# FreedomPort.net
KiCad netlist of a schematic drawn in EAGLE
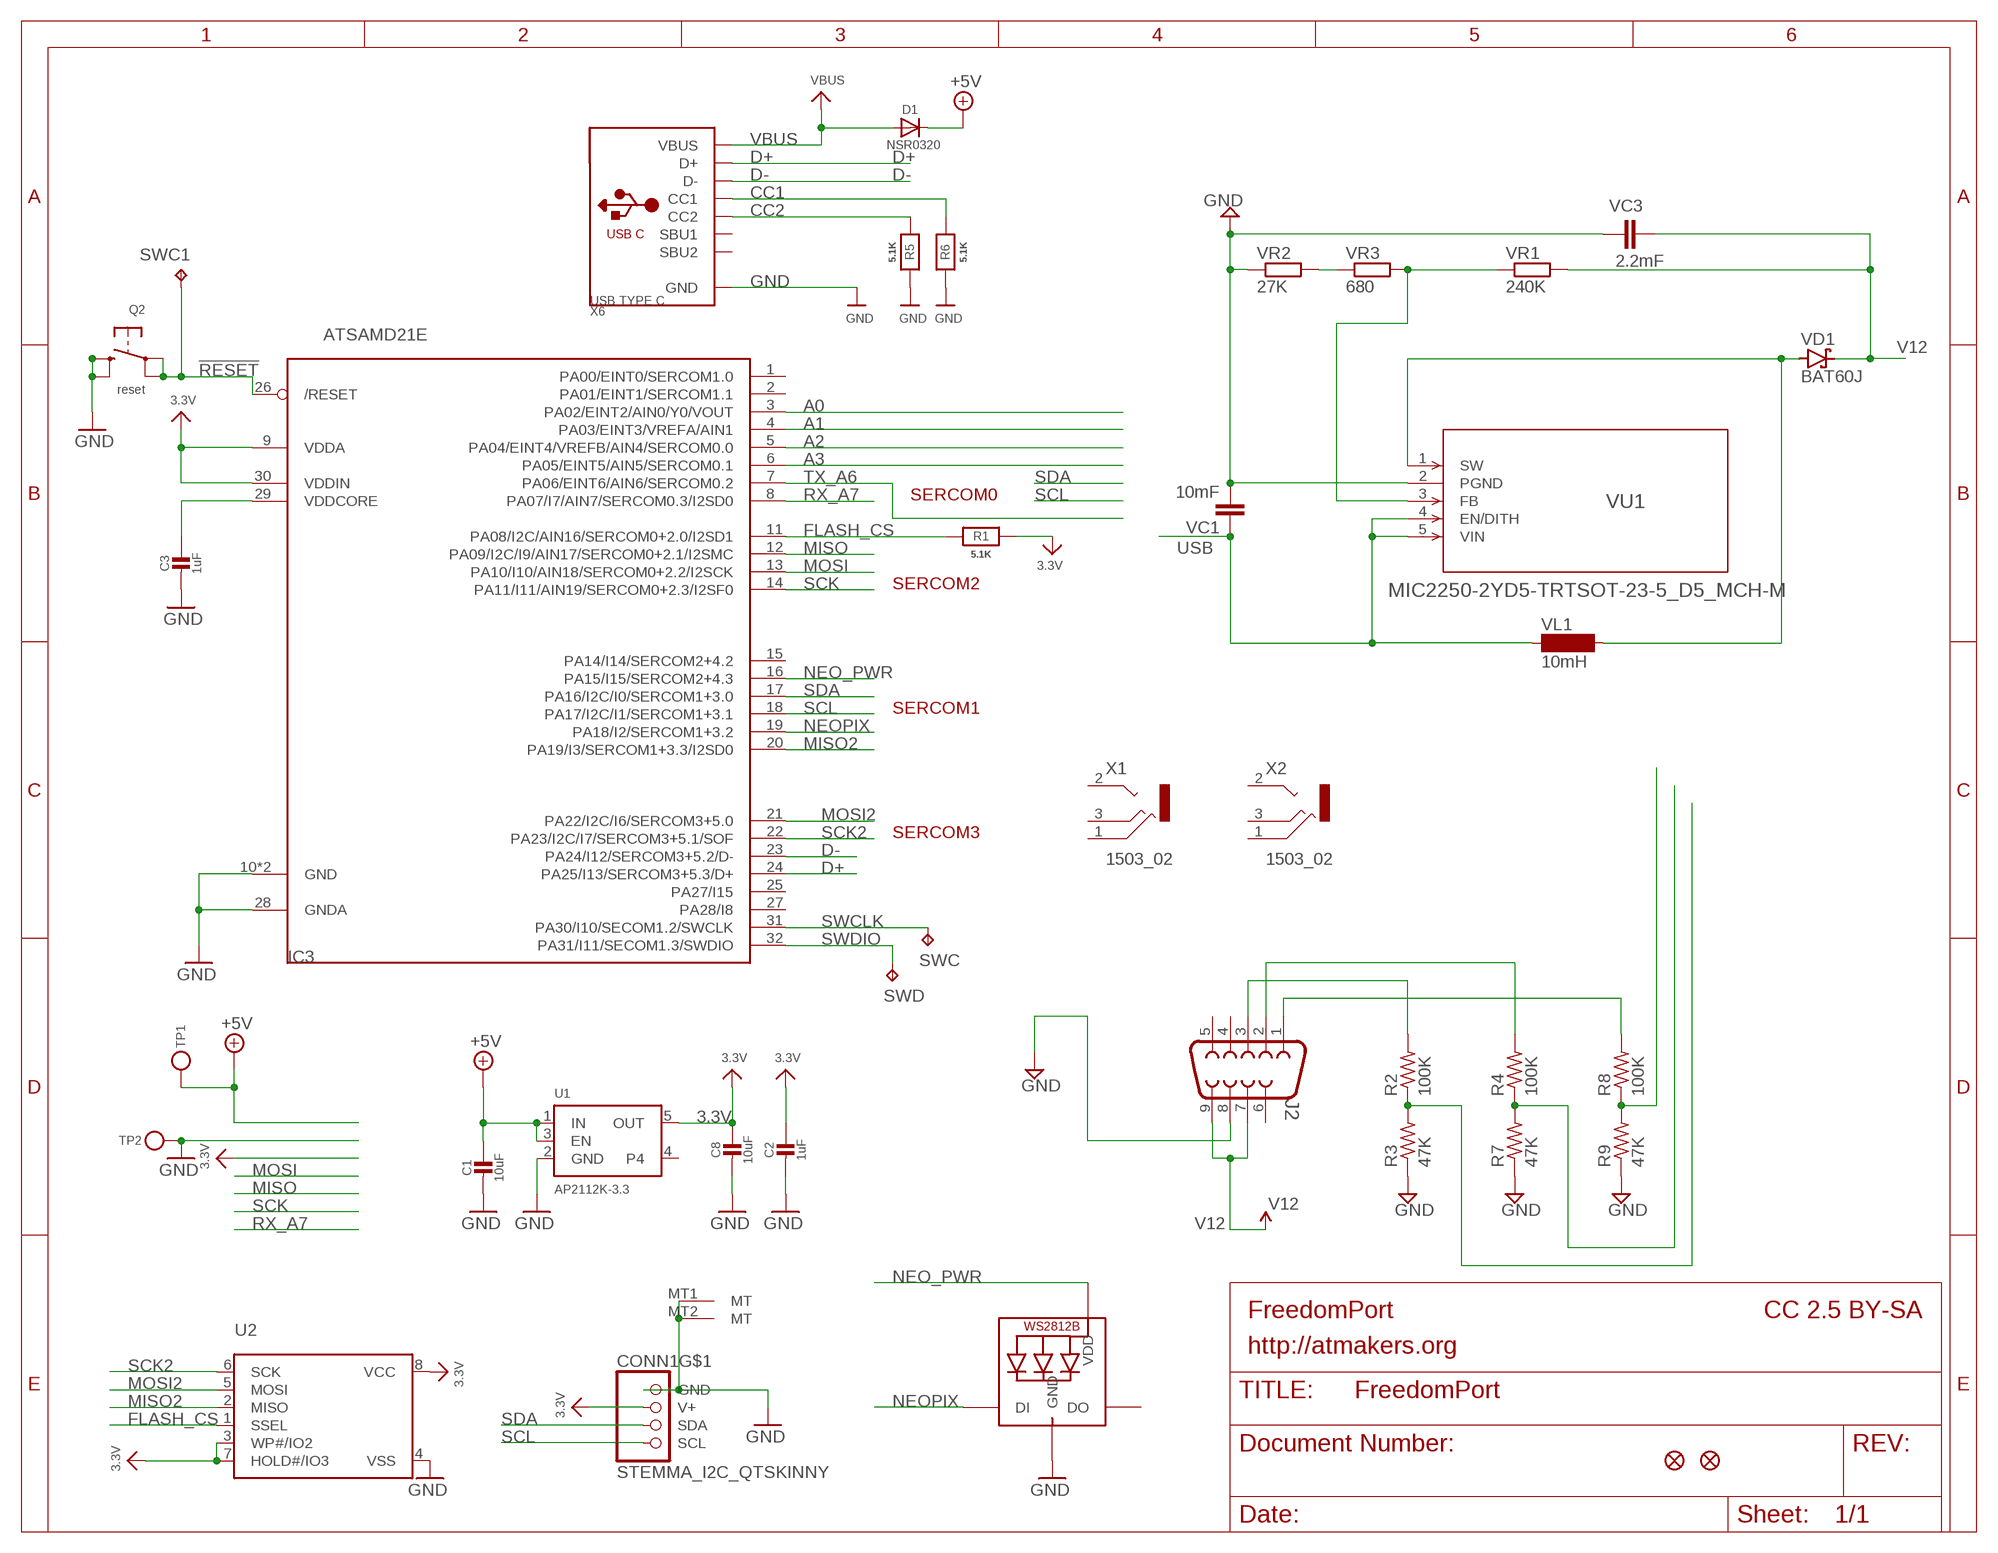
[diagram p0: schematic, sheet 1]

(export (version "E")
  (design (tool "Eeschema 10.0.6"))
  (components
    (comp (ref "C1")
      (value "10uF")
      (footprint "eagle-import:_0805MP")
      (libsource (lib "eagle-import") (part "CAP_CERAMIC_0805MP"))
    )
    (comp (ref "C2")
      (value "1uF")
      (footprint "eagle-import:_0402NO")
      (libsource (lib "eagle-import") (part "CAP_CERAMIC_0402NO"))
    )
    (comp (ref "C3")
      (value "1uF")
      (footprint "eagle-import:_0402NO")
      (libsource (lib "eagle-import") (part "CAP_CERAMIC_0402NO"))
    )
    (comp (ref "C8")
      (value "10uF")
      (footprint "eagle-import:_0805MP")
      (libsource (lib "eagle-import") (part "CAP_CERAMIC_0805MP"))
    )
    (comp (ref "CONN1")
      (value "STEMMA_I2C_QTSKINNY")
      (footprint "eagle-import:JST_SH4_SKINNY")
      (libsource (lib "eagle-import") (part "STEMMA_I2C_QTSKINNY"))
    )
    (comp (ref "D1")
      (value "NSR0320")
      (footprint "eagle-import:SOD-323_MINI")
      (libsource (lib "eagle-import") (part "DIODE_SOD323MINI"))
    )
    (comp (ref "IC3")
      (value "ATSAMD21E")
      (footprint "eagle-import:QFN32_5MM")
      (libsource (lib "eagle-import") (part "ATSAMD21E"))
    )
    (comp (ref "J2")
      (value "DB9MALE")
      (footprint "eagle-import:DB9_MALE")
      (libsource (lib "eagle-import") (part "DB9MALE"))
    )
    (comp (ref "LED1")
      (value "WS2812B_SK6805_1515")
      (footprint "eagle-import:SK6805_1515")
      (libsource (lib "eagle-import") (part "WS2812B_SK6805_1515"))
    )
    (comp (ref "Q2")
      (value "reset")
      (footprint "eagle-import:BTN_KMR2_4.6X2.8")
      (libsource (lib "eagle-import") (part "SWITCH_TACT_SMT4.6X2.8"))
    )
    (comp (ref "R1")
      (value "5.1K")
      (footprint "eagle-import:_0402NO")
      (libsource (lib "eagle-import") (part "RESISTOR_0402NO"))
    )
    (comp (ref "R2")
      (value "100K")
      (footprint "eagle-import:R0805")
      (libsource (lib "eagle-import") (part "R-US_R0805"))
    )
    (comp (ref "R3")
      (value "47K")
      (footprint "eagle-import:R0805")
      (libsource (lib "eagle-import") (part "R-US_R0805"))
    )
    (comp (ref "R4")
      (value "100K")
      (footprint "eagle-import:R0805")
      (libsource (lib "eagle-import") (part "R-US_R0805"))
    )
    (comp (ref "R5")
      (value "5.1K")
      (footprint "eagle-import:_0402NO")
      (libsource (lib "eagle-import") (part "RESISTOR_0402NO"))
    )
    (comp (ref "R6")
      (value "5.1K")
      (footprint "eagle-import:_0402NO")
      (libsource (lib "eagle-import") (part "RESISTOR_0402NO"))
    )
    (comp (ref "R7")
      (value "47K")
      (footprint "eagle-import:R0805")
      (libsource (lib "eagle-import") (part "R-US_R0805"))
    )
    (comp (ref "R8")
      (value "100K")
      (footprint "eagle-import:R0805")
      (libsource (lib "eagle-import") (part "R-US_R0805"))
    )
    (comp (ref "R9")
      (value "47K")
      (footprint "eagle-import:R0805")
      (libsource (lib "eagle-import") (part "R-US_R0805"))
    )
    (comp (ref "SWC")
      (value "TPB1,27")
      (footprint "eagle-import:B1,27")
      (libsource (lib "eagle-import") (part "TPB1,27"))
    )
    (comp (ref "SWC1")
      (value "TPB1,27")
      (footprint "eagle-import:B1,27")
      (libsource (lib "eagle-import") (part "TPB1,27"))
    )
    (comp (ref "SWD")
      (value "TPB1,27")
      (footprint "eagle-import:B1,27")
      (libsource (lib "eagle-import") (part "TPB1,27"))
    )
    (comp (ref "TP1")
      (value "TESTPOINT_1X3")
      (footprint "eagle-import:TESTPOINT_RECT_1X3MM")
      (libsource (lib "eagle-import") (part "TESTPOINT_1X3"))
    )
    (comp (ref "TP2")
      (value "TESTPOINT_1X3")
      (footprint "eagle-import:TESTPOINT_RECT_1X3MM")
      (libsource (lib "eagle-import") (part "TESTPOINT_1X3"))
    )
    (comp (ref "U$6")
      (value "FIDUCIAL_1MM")
      (footprint "eagle-import:FIDUCIAL_1MM")
      (libsource (lib "eagle-import") (part "FIDUCIAL_1MM"))
    )
    (comp (ref "U$8")
      (value "FIDUCIAL_1MM")
      (footprint "eagle-import:FIDUCIAL_1MM")
      (libsource (lib "eagle-import") (part "FIDUCIAL_1MM"))
    )
    (comp (ref "U1")
      (value "AP2112K-3.3")
      (footprint "eagle-import:SOT23-5")
      (libsource (lib "eagle-import") (part "VREG_SOT23-5"))
    )
    (comp (ref "U2")
      (value "SPIFLASH_8PIN")
      (footprint "eagle-import:SOIC8_150MIL")
      (libsource (lib "eagle-import") (part "SPIFLASH_8PIN"))
    )
    (comp (ref "VC1")
      (value "10mF")
      (footprint "eagle-import:C0805")
      (libsource (lib "eagle-import") (part "C-EUC0805"))
    )
    (comp (ref "VC3")
      (value "2.2mF")
      (footprint "eagle-import:C0805")
      (libsource (lib "eagle-import") (part "C-EUC0805"))
    )
    (comp (ref "VD1")
      (value "BAT60J")
      (footprint "eagle-import:SOD323_ST")
      (libsource (lib "eagle-import") (part "BAT60J"))
    )
    (comp (ref "VL1")
      (value "10mH")
      (footprint "eagle-import:MS50")
      (libsource (lib "eagle-import") (part "MS50"))
    )
    (comp (ref "VR1")
      (value "240K")
      (footprint "eagle-import:R0805W")
      (libsource (lib "eagle-import") (part "R-EU_R0805W"))
    )
    (comp (ref "VR2")
      (value "27K")
      (footprint "eagle-import:R0805W")
      (libsource (lib "eagle-import") (part "R-EU_R0805W"))
    )
    (comp (ref "VR3")
      (value "680")
      (footprint "eagle-import:R0805W")
      (libsource (lib "eagle-import") (part "R-EU_R0805W"))
    )
    (comp (ref "VU1")
      (value "MIC2250-2YD5-TRTSOT-23-5_D5_MCH-M")
      (footprint "eagle-import:TSOT-23-5_D5_MCH-M")
      (fields
        (field (name "MANUFACTURER_PART_NUMBER") "MIC2250-2YD5-TR")
        (field (name "COPYRIGHT") "Copyright (C) 2018 Accelerated Designs. All rights reserved")
      )
      (libsource (lib "eagle-import") (part "MIC2250-2YD5-TRTSOT-23-5_D5_MCH-M"))
    )
    (comp (ref "X1")
      (value "1503_02")
      (footprint "eagle-import:1503_02")
      (libsource (lib "eagle-import") (part "1503_02"))
    )
    (comp (ref "X2")
      (value "1503_02")
      (footprint "eagle-import:1503_02")
      (libsource (lib "eagle-import") (part "1503_02"))
    )
    (comp (ref "X6")
      (value "USB TYPE C")
      (footprint "eagle-import:USB_C_CUSB31-CFM2AX-01-X")
      (libsource (lib "eagle-import") (part "USB_C"))
    )
  )
  (nets
    (net (code "1") (name "+5V") (class "Default")
      (node (ref "C1") (pin "1") (pinfunction "1_1") (pintype "passive"))
      (node (ref "D1") (pin "C") (pinfunction "C_C") (pintype "passive"))
      (node (ref "TP1") (pin "P$1") (pinfunction "P$1_P$1") (pintype "bidirectional"))
      (node (ref "U1") (pin "1") (pinfunction "IN_1") (pintype "power_in"))
      (node (ref "U1") (pin "3") (pinfunction "EN_3") (pintype "input"))
    )
    (net (code "2") (name "/A0") (class "Default")
      (node (ref "IC3") (pin "3") (pinfunction "PA02/EINT2/AIN0/Y0/VOUT_3") (pintype "bidirectional"))
    )
    (net (code "3") (name "/A1") (class "Default")
      (node (ref "IC3") (pin "4") (pinfunction "PA03/EINT3/VREFA/AIN1_4") (pintype "bidirectional"))
    )
    (net (code "4") (name "/A2") (class "Default")
      (node (ref "IC3") (pin "5") (pinfunction "PA04/EINT4/VREFB/AIN4/SERCOM0.0_5") (pintype "bidirectional"))
    )
    (net (code "5") (name "/A3") (class "Default")
      (node (ref "IC3") (pin "6") (pinfunction "PA05/EINT5/AIN5/SERCOM0.1_6") (pintype "bidirectional"))
    )
    (net (code "6") (name "/CC1") (class "Default")
      (node (ref "R6") (pin "2") (pinfunction "2_2") (pintype "passive"))
      (node (ref "X6") (pin "A5") (pinfunction "CC1_A5") (pintype "bidirectional"))
    )
    (net (code "7") (name "/CC2") (class "Default")
      (node (ref "R5") (pin "2") (pinfunction "2_2") (pintype "passive"))
      (node (ref "X6") (pin "B5") (pinfunction "CC2_B5") (pintype "bidirectional"))
    )
    (net (code "8") (name "/D+") (class "Default")
      (node (ref "IC3") (pin "24") (pinfunction "PA25/I13/SERCOM3+5.3/D+_24") (pintype "bidirectional"))
      (node (ref "X6") (pin "A6") (pinfunction "D+_A6") (pintype "bidirectional"))
      (node (ref "X6") (pin "B6") (pinfunction "D+_B6") (pintype "bidirectional"))
    )
    (net (code "9") (name "/D-") (class "Default")
      (node (ref "IC3") (pin "23") (pinfunction "PA24/I12/SERCOM3+5.2/D-_23") (pintype "bidirectional"))
      (node (ref "X6") (pin "A7") (pinfunction "D-_A7") (pintype "bidirectional"))
      (node (ref "X6") (pin "B7") (pinfunction "D-_B7") (pintype "bidirectional"))
    )
    (net (code "10") (name "/FLASH_CS") (class "Default")
      (node (ref "IC3") (pin "11") (pinfunction "PA08/I2C/AIN16/SERCOM0+2.0/I2SD1_11") (pintype "bidirectional"))
      (node (ref "R1") (pin "2") (pinfunction "2_2") (pintype "passive"))
      (node (ref "U2") (pin "1") (pinfunction "SSEL_1") (pintype "bidirectional"))
    )
    (net (code "11") (name "/MISO") (class "Default")
      (node (ref "IC3") (pin "12") (pinfunction "PA09/I2C/I9/AIN17/SERCOM0+2.1/I2SMC_12") (pintype "bidirectional"))
    )
    (net (code "12") (name "/MISO2") (class "Default")
      (node (ref "IC3") (pin "20") (pinfunction "PA19/I3/SERCOM1+3.3/I2SD0_20") (pintype "bidirectional"))
      (node (ref "U2") (pin "2") (pinfunction "MISO_2") (pintype "bidirectional"))
    )
    (net (code "13") (name "/MOSI") (class "Default")
      (node (ref "IC3") (pin "13") (pinfunction "PA10/I10/AIN18/SERCOM0+2.2/I2SCK_13") (pintype "bidirectional"))
    )
    (net (code "14") (name "/MOSI2") (class "Default")
      (node (ref "IC3") (pin "21") (pinfunction "PA22/I2C/I6/SERCOM3+5.0_21") (pintype "bidirectional"))
      (node (ref "U2") (pin "5") (pinfunction "MOSI_5") (pintype "bidirectional"))
    )
    (net (code "15") (name "/NEOPIX") (class "Default")
      (node (ref "IC3") (pin "19") (pinfunction "PA18/I2/SERCOM1+3.2_19") (pintype "bidirectional"))
      (node (ref "LED1") (pin "1") (pinfunction "DI_1") (pintype "input"))
    )
    (net (code "16") (name "/NEO_PWR") (class "Default")
      (node (ref "IC3") (pin "16") (pinfunction "PA15/I15/SERCOM2+4.3_16") (pintype "bidirectional"))
      (node (ref "LED1") (pin "2") (pinfunction "VDD_2") (pintype "power_in"))
    )
    (net (code "17") (name "/RX_A7") (class "Default")
      (node (ref "IC3") (pin "8") (pinfunction "PA07/I7/AIN7/SERCOM0.3/I2SD0_8") (pintype "bidirectional"))
    )
    (net (code "18") (name "/SCK") (class "Default")
      (node (ref "IC3") (pin "14") (pinfunction "PA11/I11/AIN19/SERCOM0+2.3/I2SF0_14") (pintype "bidirectional"))
    )
    (net (code "19") (name "/SCK2") (class "Default")
      (node (ref "IC3") (pin "22") (pinfunction "PA23/I2C/I7/SERCOM3+5.1/SOF_22") (pintype "bidirectional"))
      (node (ref "U2") (pin "6") (pinfunction "SCK_6") (pintype "bidirectional"))
    )
    (net (code "20") (name "/SCL") (class "Default")
      (node (ref "CONN1") (pin "4") (pinfunction "SCL_4") (pintype "passive"))
      (node (ref "IC3") (pin "18") (pinfunction "PA17/I2C/I1/SERCOM1+3.1_18") (pintype "bidirectional"))
    )
    (net (code "21") (name "/SDA") (class "Default")
      (node (ref "CONN1") (pin "3") (pinfunction "SDA_3") (pintype "passive"))
      (node (ref "IC3") (pin "17") (pinfunction "PA16/I2C/I0/SERCOM1+3.0_17") (pintype "bidirectional"))
    )
    (net (code "22") (name "/SWCLK") (class "Default")
      (node (ref "IC3") (pin "31") (pinfunction "PA30/I10/SECOM1.2/SWCLK_31") (pintype "bidirectional"))
      (node (ref "SWC") (pin "TP") (pinfunction "TP_TP") (pintype "input"))
    )
    (net (code "23") (name "/SWDIO") (class "Default")
      (node (ref "IC3") (pin "32") (pinfunction "PA31/I11/SECOM1.3/SWDIO_32") (pintype "bidirectional"))
      (node (ref "SWD") (pin "TP") (pinfunction "TP_TP") (pintype "input"))
    )
    (net (code "24") (name "/TX_A6") (class "Default")
      (node (ref "IC3") (pin "7") (pinfunction "PA06/EINT6/AIN6/SERCOM0.2_7") (pintype "bidirectional"))
    )
    (net (code "25") (name "/USB") (class "Default")
      (node (ref "VC1") (pin "1") (pinfunction "1_1") (pintype "passive"))
      (node (ref "VL1") (pin "1") (pinfunction "1_1") (pintype "passive"))
      (node (ref "VU1") (pin "4") (pinfunction "EN/DITH_4") (pintype "input"))
      (node (ref "VU1") (pin "5") (pinfunction "VIN_5") (pintype "input"))
    )
    (net (code "26") (name "/~{RESET}") (class "Default")
      (node (ref "IC3") (pin "26") (pinfunction "/RESET_26") (pintype "bidirectional"))
      (node (ref "Q2") (pin "A") (pinfunction "P_A") (pintype "passive"))
      (node (ref "Q2") (pin "A'") (pinfunction "P1_A'") (pintype "passive"))
      (node (ref "SWC1") (pin "TP") (pinfunction "TP_TP") (pintype "input"))
    )
    (net (code "27") (name "3.3V") (class "Default")
      (node (ref "C2") (pin "1") (pinfunction "1_1") (pintype "passive"))
      (node (ref "C8") (pin "1") (pinfunction "1_1") (pintype "passive"))
      (node (ref "CONN1") (pin "2") (pinfunction "V+_2") (pintype "passive"))
      (node (ref "IC3") (pin "30") (pinfunction "VDDIN_30") (pintype "power_in"))
      (node (ref "IC3") (pin "9") (pinfunction "VDDA_9") (pintype "power_in"))
      (node (ref "R1") (pin "1") (pinfunction "1_1") (pintype "passive"))
      (node (ref "U1") (pin "5") (pinfunction "OUT_5") (pintype "power_in"))
      (node (ref "U2") (pin "3") (pinfunction "WP#/IO2_3") (pintype "bidirectional"))
      (node (ref "U2") (pin "7") (pinfunction "HOLD#/IO3_7") (pintype "bidirectional"))
      (node (ref "U2") (pin "8") (pinfunction "VCC_8") (pintype "bidirectional"))
    )
    (net (code "28") (name "GND") (class "Default")
      (node (ref "C1") (pin "2") (pinfunction "2_2") (pintype "passive"))
      (node (ref "C2") (pin "2") (pinfunction "2_2") (pintype "passive"))
      (node (ref "C3") (pin "2") (pinfunction "2_2") (pintype "passive"))
      (node (ref "C8") (pin "2") (pinfunction "2_2") (pintype "passive"))
      (node (ref "CONN1") (pin "1") (pinfunction "GND_1") (pintype "passive"))
      (node (ref "CONN1") (pin "MT1") (pinfunction "MT_MT1") (pintype "bidirectional"))
      (node (ref "CONN1") (pin "MT2") (pinfunction "MT_MT2") (pintype "bidirectional"))
      (node (ref "IC3") (pin "10") (pinfunction "GND_10") (pintype "power_in"))
      (node (ref "IC3") (pin "28") (pinfunction "GNDA_28") (pintype "power_in"))
      (node (ref "IC3") (pin "33") (pinfunction "GND_33") (pintype "power_in"))
      (node (ref "J2") (pin "8") (pinfunction "8_8") (pintype "passive"))
      (node (ref "LED1") (pin "4") (pinfunction "GND_4") (pintype "power_in"))
      (node (ref "Q2") (pin "B") (pinfunction "S_B") (pintype "passive"))
      (node (ref "Q2") (pin "B'") (pinfunction "S1_B'") (pintype "passive"))
      (node (ref "R3") (pin "1") (pinfunction "1_1") (pintype "passive"))
      (node (ref "R5") (pin "1") (pinfunction "1_1") (pintype "passive"))
      (node (ref "R6") (pin "1") (pinfunction "1_1") (pintype "passive"))
      (node (ref "R7") (pin "1") (pinfunction "1_1") (pintype "passive"))
      (node (ref "R9") (pin "1") (pinfunction "1_1") (pintype "passive"))
      (node (ref "TP2") (pin "P$1") (pinfunction "P$1_P$1") (pintype "bidirectional"))
      (node (ref "U1") (pin "2") (pinfunction "GND_2") (pintype "power_in"))
      (node (ref "U2") (pin "4") (pinfunction "VSS_4") (pintype "bidirectional"))
      (node (ref "VC1") (pin "2") (pinfunction "2_2") (pintype "passive"))
      (node (ref "VC3") (pin "1") (pinfunction "1_1") (pintype "passive"))
      (node (ref "VR2") (pin "1") (pinfunction "1_1") (pintype "passive"))
      (node (ref "VU1") (pin "2") (pinfunction "PGND_2") (pintype "power_in"))
      (node (ref "X6") (pin "A1B12") (pinfunction "GND_A1B12") (pintype "power_in"))
      (node (ref "X6") (pin "B1A12") (pinfunction "GND_B1A12") (pintype "power_in"))
    )
    (net (code "29") (name "Net-(IC3-VDDCORE)") (class "Default")
      (node (ref "C3") (pin "1") (pinfunction "1_1") (pintype "passive"))
      (node (ref "IC3") (pin "29") (pinfunction "VDDCORE_29") (pintype "power_in"))
    )
    (net (code "30") (name "Net-(J2-Pad1)") (class "Default")
      (node (ref "J2") (pin "1") (pinfunction "1_1") (pintype "passive"))
      (node (ref "R8") (pin "2") (pinfunction "2_2") (pintype "passive"))
    )
    (net (code "31") (name "Net-(J2-Pad2)") (class "Default")
      (node (ref "J2") (pin "2") (pinfunction "2_2") (pintype "passive"))
      (node (ref "R4") (pin "2") (pinfunction "2_2") (pintype "passive"))
    )
    (net (code "32") (name "Net-(J2-Pad3)") (class "Default")
      (node (ref "J2") (pin "3") (pinfunction "3_3") (pintype "passive"))
      (node (ref "R2") (pin "2") (pinfunction "2_2") (pintype "passive"))
    )
    (net (code "33") (name "Net-(R2-Pad1)") (class "Default")
      (node (ref "R2") (pin "1") (pinfunction "1_1") (pintype "passive"))
      (node (ref "R3") (pin "2") (pinfunction "2_2") (pintype "passive"))
    )
    (net (code "34") (name "Net-(R4-Pad1)") (class "Default")
      (node (ref "R4") (pin "1") (pinfunction "1_1") (pintype "passive"))
      (node (ref "R7") (pin "2") (pinfunction "2_2") (pintype "passive"))
    )
    (net (code "35") (name "Net-(R8-Pad1)") (class "Default")
      (node (ref "R8") (pin "1") (pinfunction "1_1") (pintype "passive"))
      (node (ref "R9") (pin "2") (pinfunction "2_2") (pintype "passive"))
    )
    (net (code "36") (name "Net-(VR2-Pad2)") (class "Default")
      (node (ref "VR2") (pin "2") (pinfunction "2_2") (pintype "passive"))
      (node (ref "VR3") (pin "1") (pinfunction "1_1") (pintype "passive"))
    )
    (net (code "37") (name "Net-(VU1-FB)") (class "Default")
      (node (ref "VR1") (pin "1") (pinfunction "1_1") (pintype "passive"))
      (node (ref "VR3") (pin "2") (pinfunction "2_2") (pintype "passive"))
      (node (ref "VU1") (pin "3") (pinfunction "FB_3") (pintype "input"))
    )
    (net (code "38") (name "Net-(VU1-SW)") (class "Default")
      (node (ref "VD1") (pin "A") (pinfunction "A_A") (pintype "passive"))
      (node (ref "VL1") (pin "2") (pinfunction "2_2") (pintype "passive"))
      (node (ref "VU1") (pin "1") (pinfunction "SW_1") (pintype "input"))
    )
    (net (code "39") (name "V12") (class "Default")
      (node (ref "J2") (pin "7") (pinfunction "7_7") (pintype "passive"))
      (node (ref "J2") (pin "9") (pinfunction "9_9") (pintype "passive"))
      (node (ref "VC3") (pin "2") (pinfunction "2_2") (pintype "passive"))
      (node (ref "VD1") (pin "C") (pinfunction "C_C") (pintype "passive"))
      (node (ref "VR1") (pin "2") (pinfunction "2_2") (pintype "passive"))
    )
    (net (code "40") (name "VBUS") (class "Default")
      (node (ref "D1") (pin "A") (pinfunction "A_A") (pintype "passive"))
      (node (ref "X6") (pin "A4B9") (pinfunction "VBUS_A4B9") (pintype "power_in"))
      (node (ref "X6") (pin "B4A9") (pinfunction "VBUS_B4A9") (pintype "power_in"))
    )
    (net (code "41") (name "unconnected-(IC3-PA00{slash}EINT0{slash}SERCOM1.0-Pad1)") (class "Default")
      (node (ref "IC3") (pin "1") (pinfunction "PA00/EINT0/SERCOM1.0_1") (pintype "bidirectional"))
    )
    (net (code "42") (name "unconnected-(IC3-PA01{slash}EINT1{slash}SERCOM1.1-Pad2)") (class "Default")
      (node (ref "IC3") (pin "2") (pinfunction "PA01/EINT1/SERCOM1.1_2") (pintype "bidirectional"))
    )
    (net (code "43") (name "unconnected-(IC3-PA14{slash}I14{slash}SERCOM2+4.2-Pad15)") (class "Default")
      (node (ref "IC3") (pin "15") (pinfunction "PA14/I14/SERCOM2+4.2_15") (pintype "bidirectional"))
    )
    (net (code "44") (name "unconnected-(IC3-PA27{slash}I15-Pad25)") (class "Default")
      (node (ref "IC3") (pin "25") (pinfunction "PA27/I15_25") (pintype "bidirectional"))
    )
    (net (code "45") (name "unconnected-(IC3-PA28{slash}I8-Pad27)") (class "Default")
      (node (ref "IC3") (pin "27") (pinfunction "PA28/I8_27") (pintype "bidirectional"))
    )
    (net (code "46") (name "unconnected-(J2-Pad4)") (class "Default")
      (node (ref "J2") (pin "4") (pinfunction "4_4") (pintype "passive"))
    )
    (net (code "47") (name "unconnected-(J2-Pad5)") (class "Default")
      (node (ref "J2") (pin "5") (pinfunction "5_5") (pintype "passive"))
    )
    (net (code "48") (name "unconnected-(J2-Pad6)") (class "Default")
      (node (ref "J2") (pin "6") (pinfunction "6_6") (pintype "passive"))
    )
    (net (code "49") (name "unconnected-(LED1-DO-Pad3)") (class "Default")
      (node (ref "LED1") (pin "3") (pinfunction "DO_3") (pintype "output"))
    )
    (net (code "50") (name "unconnected-(U1-P4-Pad4)") (class "Default")
      (node (ref "U1") (pin "4") (pinfunction "P4_4") (pintype "bidirectional"))
    )
    (net (code "51") (name "unconnected-(X1-2-Pad2@2)") (class "Default")
      (node (ref "X1") (pin "2@2") (pinfunction "2_2@2") (pintype "passive"))
    )
    (net (code "52") (name "unconnected-(X1-Pad1)") (class "Default")
      (node (ref "X1") (pin "1") (pinfunction "1_1") (pintype "passive"))
    )
    (net (code "53") (name "unconnected-(X1-Pad2)") (class "Default")
      (node (ref "X1") (pin "2") (pinfunction "2_2") (pintype "passive"))
    )
    (net (code "54") (name "unconnected-(X1-Pad3)") (class "Default")
      (node (ref "X1") (pin "3") (pinfunction "3_3") (pintype "passive"))
    )
    (net (code "55") (name "unconnected-(X2-2-Pad2@2)") (class "Default")
      (node (ref "X2") (pin "2@2") (pinfunction "2_2@2") (pintype "passive"))
    )
    (net (code "56") (name "unconnected-(X2-Pad1)") (class "Default")
      (node (ref "X2") (pin "1") (pinfunction "1_1") (pintype "passive"))
    )
    (net (code "57") (name "unconnected-(X2-Pad2)") (class "Default")
      (node (ref "X2") (pin "2") (pinfunction "2_2") (pintype "passive"))
    )
    (net (code "58") (name "unconnected-(X2-Pad3)") (class "Default")
      (node (ref "X2") (pin "3") (pinfunction "3_3") (pintype "passive"))
    )
    (net (code "59") (name "unconnected-(X6-SBU1-PadA8)") (class "Default")
      (node (ref "X6") (pin "A8") (pinfunction "SBU1_A8") (pintype "bidirectional"))
    )
    (net (code "60") (name "unconnected-(X6-SBU2-PadB8)") (class "Default")
      (node (ref "X6") (pin "B8") (pinfunction "SBU2_B8") (pintype "bidirectional"))
    )
  )
)
